# WemosD1_Feeder.net
KiCad netlist of a schematic drawn in EAGLE
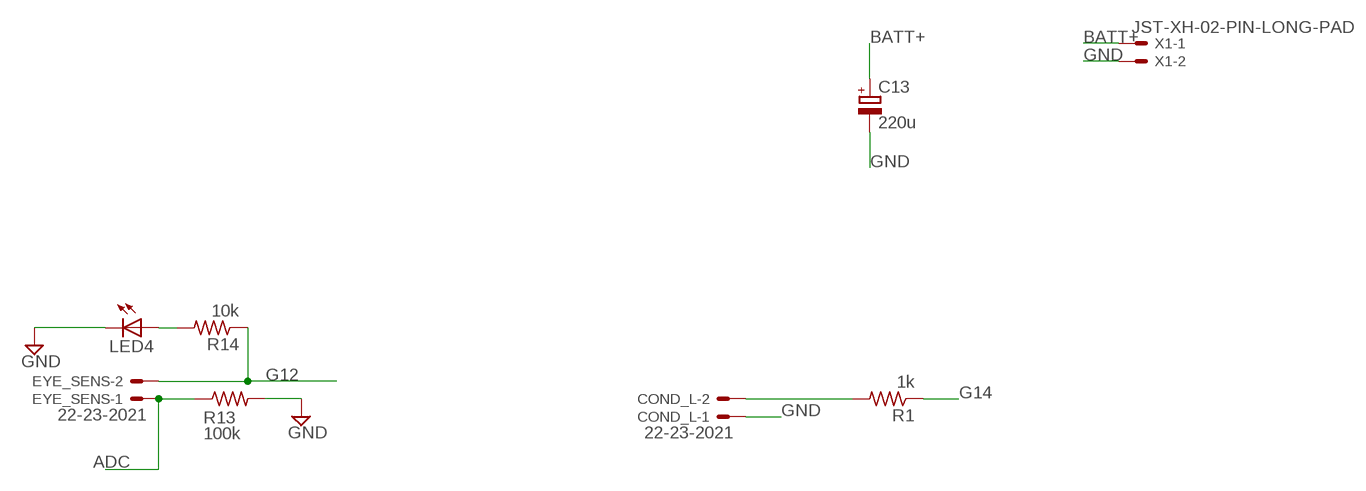
[diagram p0: schematic, sheet 1]
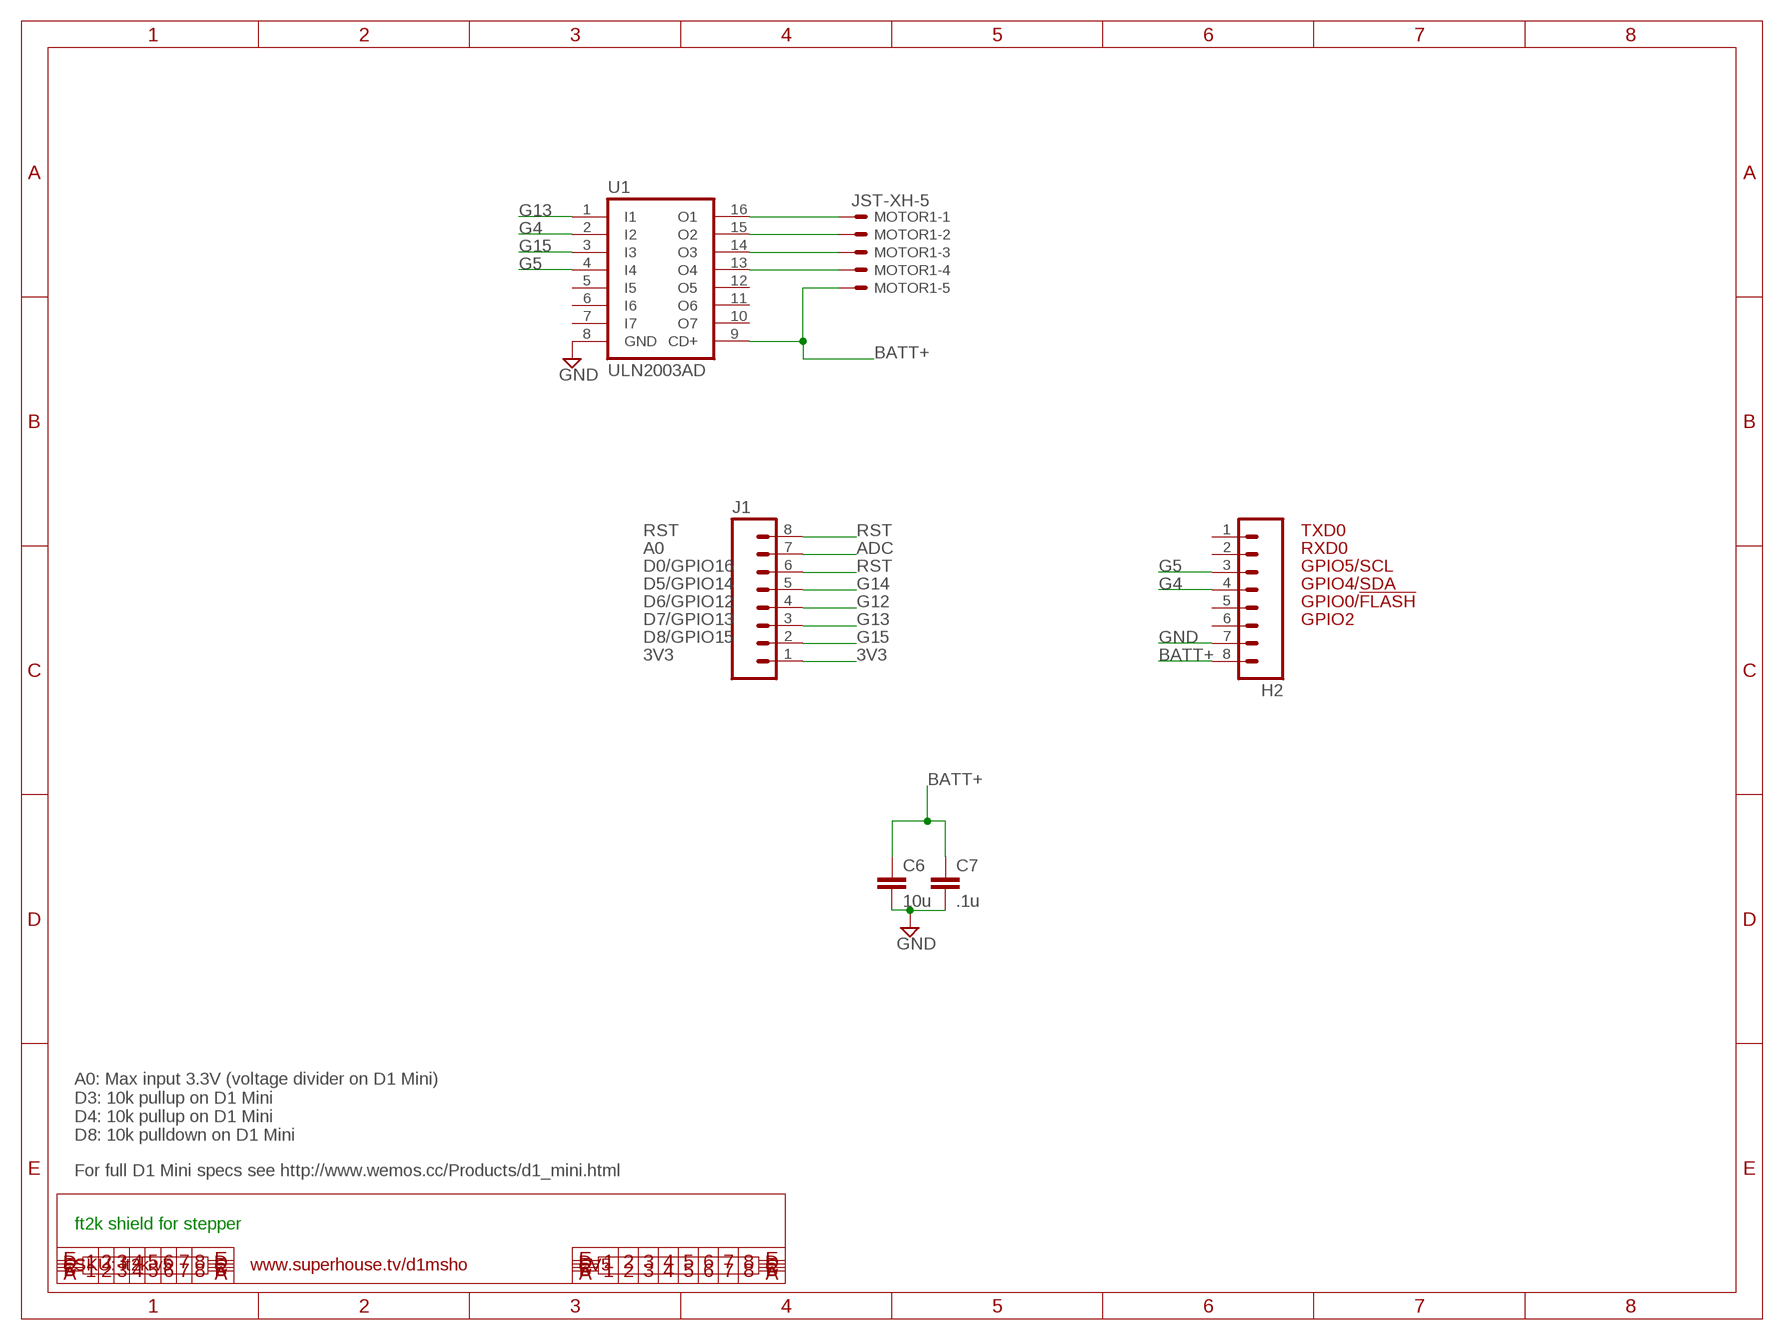
[diagram p1: schematic, sheet 2]

(export (version "E")
  (design (tool "Eeschema 10.0.6"))
  (components
    (comp (ref "C6")
      (value "10u")
      (footprint "eagle-import:C0603")
      (libsource (lib "eagle-import") (part "C-EUC0603"))
    )
    (comp (ref "C7")
      (value ".1u")
      (footprint "eagle-import:C0603")
      (libsource (lib "eagle-import") (part "C-EUC0603"))
    )
    (comp (ref "H2")
      (value "M08")
      (footprint "eagle-import:1X08")
      (libsource (lib "eagle-import") (part "freetronics-original_M08"))
    )
    (comp (ref "J1")
      (value "M08")
      (footprint "eagle-import:1X08_ROUND")
      (libsource (lib "eagle-import") (part "M08"))
    )
    (comp (ref "MOTOR1")
      (value "JST-XH-5")
      (footprint "eagle-import:JST-XH-5P")
      (libsource (lib "eagle-import") (part "JST-XH-5"))
    )
    (comp (ref "U1")
      (value "ULN2003AD")
      (footprint "eagle-import:SO16")
      (libsource (lib "eagle-import") (part "ULN2003AD"))
    )
    (comp (ref "C13")
      (value "220u")
      (footprint "eagle-import:E2,5-7")
      (libsource (lib "eagle-import") (part "CPOL-EUE2.5-7"))
    )
    (comp (ref "COND_L")
      (value "22-23-2021")
      (footprint "eagle-import:22-23-2021")
      (fields (field (name "MF") "MOLEX"))
      (libsource (lib "eagle-import") (part "22-23-2021"))
    )
    (comp (ref "EYE_SENS")
      (value "22-23-2021")
      (footprint "eagle-import:22-23-2021")
      (fields (field (name "MF") "MOLEX"))
      (libsource (lib "eagle-import") (part "22-23-2021"))
    )
    (comp (ref "LED4")
      (value "LED5MM")
      (footprint "eagle-import:LED5MM")
      (libsource (lib "eagle-import") (part "LED5MM"))
    )
    (comp (ref "R1")
      (value "1k")
      (footprint "eagle-import:R0603")
      (libsource (lib "eagle-import") (part "R-US_R0603"))
    )
    (comp (ref "R13")
      (value "100k")
      (footprint "eagle-import:R0603")
      (libsource (lib "eagle-import") (part "R-US_R0603"))
    )
    (comp (ref "R14")
      (value "10k")
      (footprint "eagle-import:R0603")
      (libsource (lib "eagle-import") (part "R-US_R0603"))
    )
    (comp (ref "X1")
      (value "JST-XH-02-PIN-LONG-PAD")
      (footprint "eagle-import:JST-XH-02-PACKAGE-LONG-PAD")
      (libsource (lib "eagle-import") (part "JST-XH-02-PIN-LONG-PAD"))
    )
  )
  (nets
    (net (code "1") (name "3V3") (class "Default")
      (node (ref "J1") (pin "1") (pinfunction "1_1") (pintype "passive"))
    )
    (net (code "2") (name "ADC") (class "Default")
      (node (ref "EYE_SENS") (pin "1") (pinfunction "S_1") (pintype "passive"))
      (node (ref "J1") (pin "7") (pinfunction "7_7") (pintype "passive"))
      (node (ref "R13") (pin "1") (pinfunction "1_1") (pintype "passive"))
    )
    (net (code "3") (name "BATT+") (class "Default")
      (node (ref "C13") (pin "+") (pinfunction "+_+") (pintype "passive"))
      (node (ref "C6") (pin "1") (pinfunction "1_1") (pintype "passive"))
      (node (ref "C7") (pin "1") (pinfunction "1_1") (pintype "passive"))
      (node (ref "H2") (pin "8") (pinfunction "8_8") (pintype "passive"))
      (node (ref "MOTOR1") (pin "P$5") (pinfunction "S_P$5") (pintype "passive"))
      (node (ref "U1") (pin "9") (pinfunction "CD+_9") (pintype "passive"))
      (node (ref "X1") (pin "1") (pinfunction "S_1") (pintype "passive"))
    )
    (net (code "4") (name "G4") (class "Default")
      (node (ref "H2") (pin "4") (pinfunction "4_4") (pintype "passive"))
      (node (ref "U1") (pin "2") (pinfunction "I2_2") (pintype "input"))
    )
    (net (code "5") (name "G5") (class "Default")
      (node (ref "H2") (pin "3") (pinfunction "3_3") (pintype "passive"))
      (node (ref "U1") (pin "4") (pinfunction "I4_4") (pintype "input"))
    )
    (net (code "6") (name "G12") (class "Default")
      (node (ref "EYE_SENS") (pin "2") (pinfunction "S_2") (pintype "passive"))
      (node (ref "J1") (pin "4") (pinfunction "4_4") (pintype "passive"))
      (node (ref "R14") (pin "1") (pinfunction "1_1") (pintype "passive"))
    )
    (net (code "7") (name "G13") (class "Default")
      (node (ref "J1") (pin "3") (pinfunction "3_3") (pintype "passive"))
      (node (ref "U1") (pin "1") (pinfunction "I1_1") (pintype "input"))
    )
    (net (code "8") (name "G14") (class "Default")
      (node (ref "J1") (pin "5") (pinfunction "5_5") (pintype "passive"))
      (node (ref "R1") (pin "1") (pinfunction "1_1") (pintype "passive"))
    )
    (net (code "9") (name "G15") (class "Default")
      (node (ref "J1") (pin "2") (pinfunction "2_2") (pintype "passive"))
      (node (ref "U1") (pin "3") (pinfunction "I3_3") (pintype "input"))
    )
    (net (code "10") (name "GND") (class "Default")
      (node (ref "C13") (pin "-") (pinfunction "-_-") (pintype "passive"))
      (node (ref "C6") (pin "2") (pinfunction "2_2") (pintype "passive"))
      (node (ref "C7") (pin "2") (pinfunction "2_2") (pintype "passive"))
      (node (ref "COND_L") (pin "1") (pinfunction "S_1") (pintype "passive"))
      (node (ref "H2") (pin "7") (pinfunction "7_7") (pintype "passive"))
      (node (ref "LED4") (pin "K") (pinfunction "C_K") (pintype "passive"))
      (node (ref "R13") (pin "2") (pinfunction "2_2") (pintype "passive"))
      (node (ref "U1") (pin "8") (pinfunction "GND_8") (pintype "power_in"))
      (node (ref "X1") (pin "2") (pinfunction "S_2") (pintype "passive"))
    )
    (net (code "11") (name "Net-(COND_LB-S)") (class "Default")
      (node (ref "COND_L") (pin "2") (pinfunction "S_2") (pintype "passive"))
      (node (ref "R1") (pin "2") (pinfunction "2_2") (pintype "passive"))
    )
    (net (code "12") (name "Net-(LED4-PadA)") (class "Default")
      (node (ref "LED4") (pin "A") (pinfunction "A_A") (pintype "passive"))
      (node (ref "R14") (pin "2") (pinfunction "2_2") (pintype "passive"))
    )
    (net (code "13") (name "Net-(MOTOR1A-S)") (class "Default")
      (node (ref "MOTOR1") (pin "P$1") (pinfunction "S_P$1") (pintype "passive"))
      (node (ref "U1") (pin "16") (pinfunction "O1_16") (pintype "open_collector"))
    )
    (net (code "14") (name "Net-(MOTOR1B-S)") (class "Default")
      (node (ref "MOTOR1") (pin "P$2") (pinfunction "S_P$2") (pintype "passive"))
      (node (ref "U1") (pin "15") (pinfunction "O2_15") (pintype "open_collector"))
    )
    (net (code "15") (name "Net-(MOTOR1C-S)") (class "Default")
      (node (ref "MOTOR1") (pin "P$3") (pinfunction "S_P$3") (pintype "passive"))
      (node (ref "U1") (pin "14") (pinfunction "O3_14") (pintype "open_collector"))
    )
    (net (code "16") (name "Net-(MOTOR1D-S)") (class "Default")
      (node (ref "MOTOR1") (pin "P$4") (pinfunction "S_P$4") (pintype "passive"))
      (node (ref "U1") (pin "13") (pinfunction "O4_13") (pintype "open_collector"))
    )
    (net (code "17") (name "RST") (class "Default")
      (node (ref "J1") (pin "6") (pinfunction "6_6") (pintype "passive"))
      (node (ref "J1") (pin "8") (pinfunction "8_8") (pintype "passive"))
    )
    (net (code "18") (name "unconnected-(H2-Pad1)") (class "Default")
      (node (ref "H2") (pin "1") (pinfunction "1_1") (pintype "passive"))
    )
    (net (code "19") (name "unconnected-(H2-Pad2)") (class "Default")
      (node (ref "H2") (pin "2") (pinfunction "2_2") (pintype "passive"))
    )
    (net (code "20") (name "unconnected-(H2-Pad5)") (class "Default")
      (node (ref "H2") (pin "5") (pinfunction "5_5") (pintype "passive"))
    )
    (net (code "21") (name "unconnected-(H2-Pad6)") (class "Default")
      (node (ref "H2") (pin "6") (pinfunction "6_6") (pintype "passive"))
    )
    (net (code "22") (name "unconnected-(U1-I5-Pad5)") (class "Default")
      (node (ref "U1") (pin "5") (pinfunction "I5_5") (pintype "input"))
    )
    (net (code "23") (name "unconnected-(U1-I6-Pad6)") (class "Default")
      (node (ref "U1") (pin "6") (pinfunction "I6_6") (pintype "input"))
    )
    (net (code "24") (name "unconnected-(U1-I7-Pad7)") (class "Default")
      (node (ref "U1") (pin "7") (pinfunction "I7_7") (pintype "input"))
    )
    (net (code "25") (name "unconnected-(U1-O5-Pad12)") (class "Default")
      (node (ref "U1") (pin "12") (pinfunction "O5_12") (pintype "open_collector"))
    )
    (net (code "26") (name "unconnected-(U1-O6-Pad11)") (class "Default")
      (node (ref "U1") (pin "11") (pinfunction "O6_11") (pintype "open_collector"))
    )
    (net (code "27") (name "unconnected-(U1-O7-Pad10)") (class "Default")
      (node (ref "U1") (pin "10") (pinfunction "O7_10") (pintype "open_collector"))
    )
  )
)
